# Output_buffer_C_and_D_Page_3.net
KiCad netlist of a schematic drawn in Altium Designer
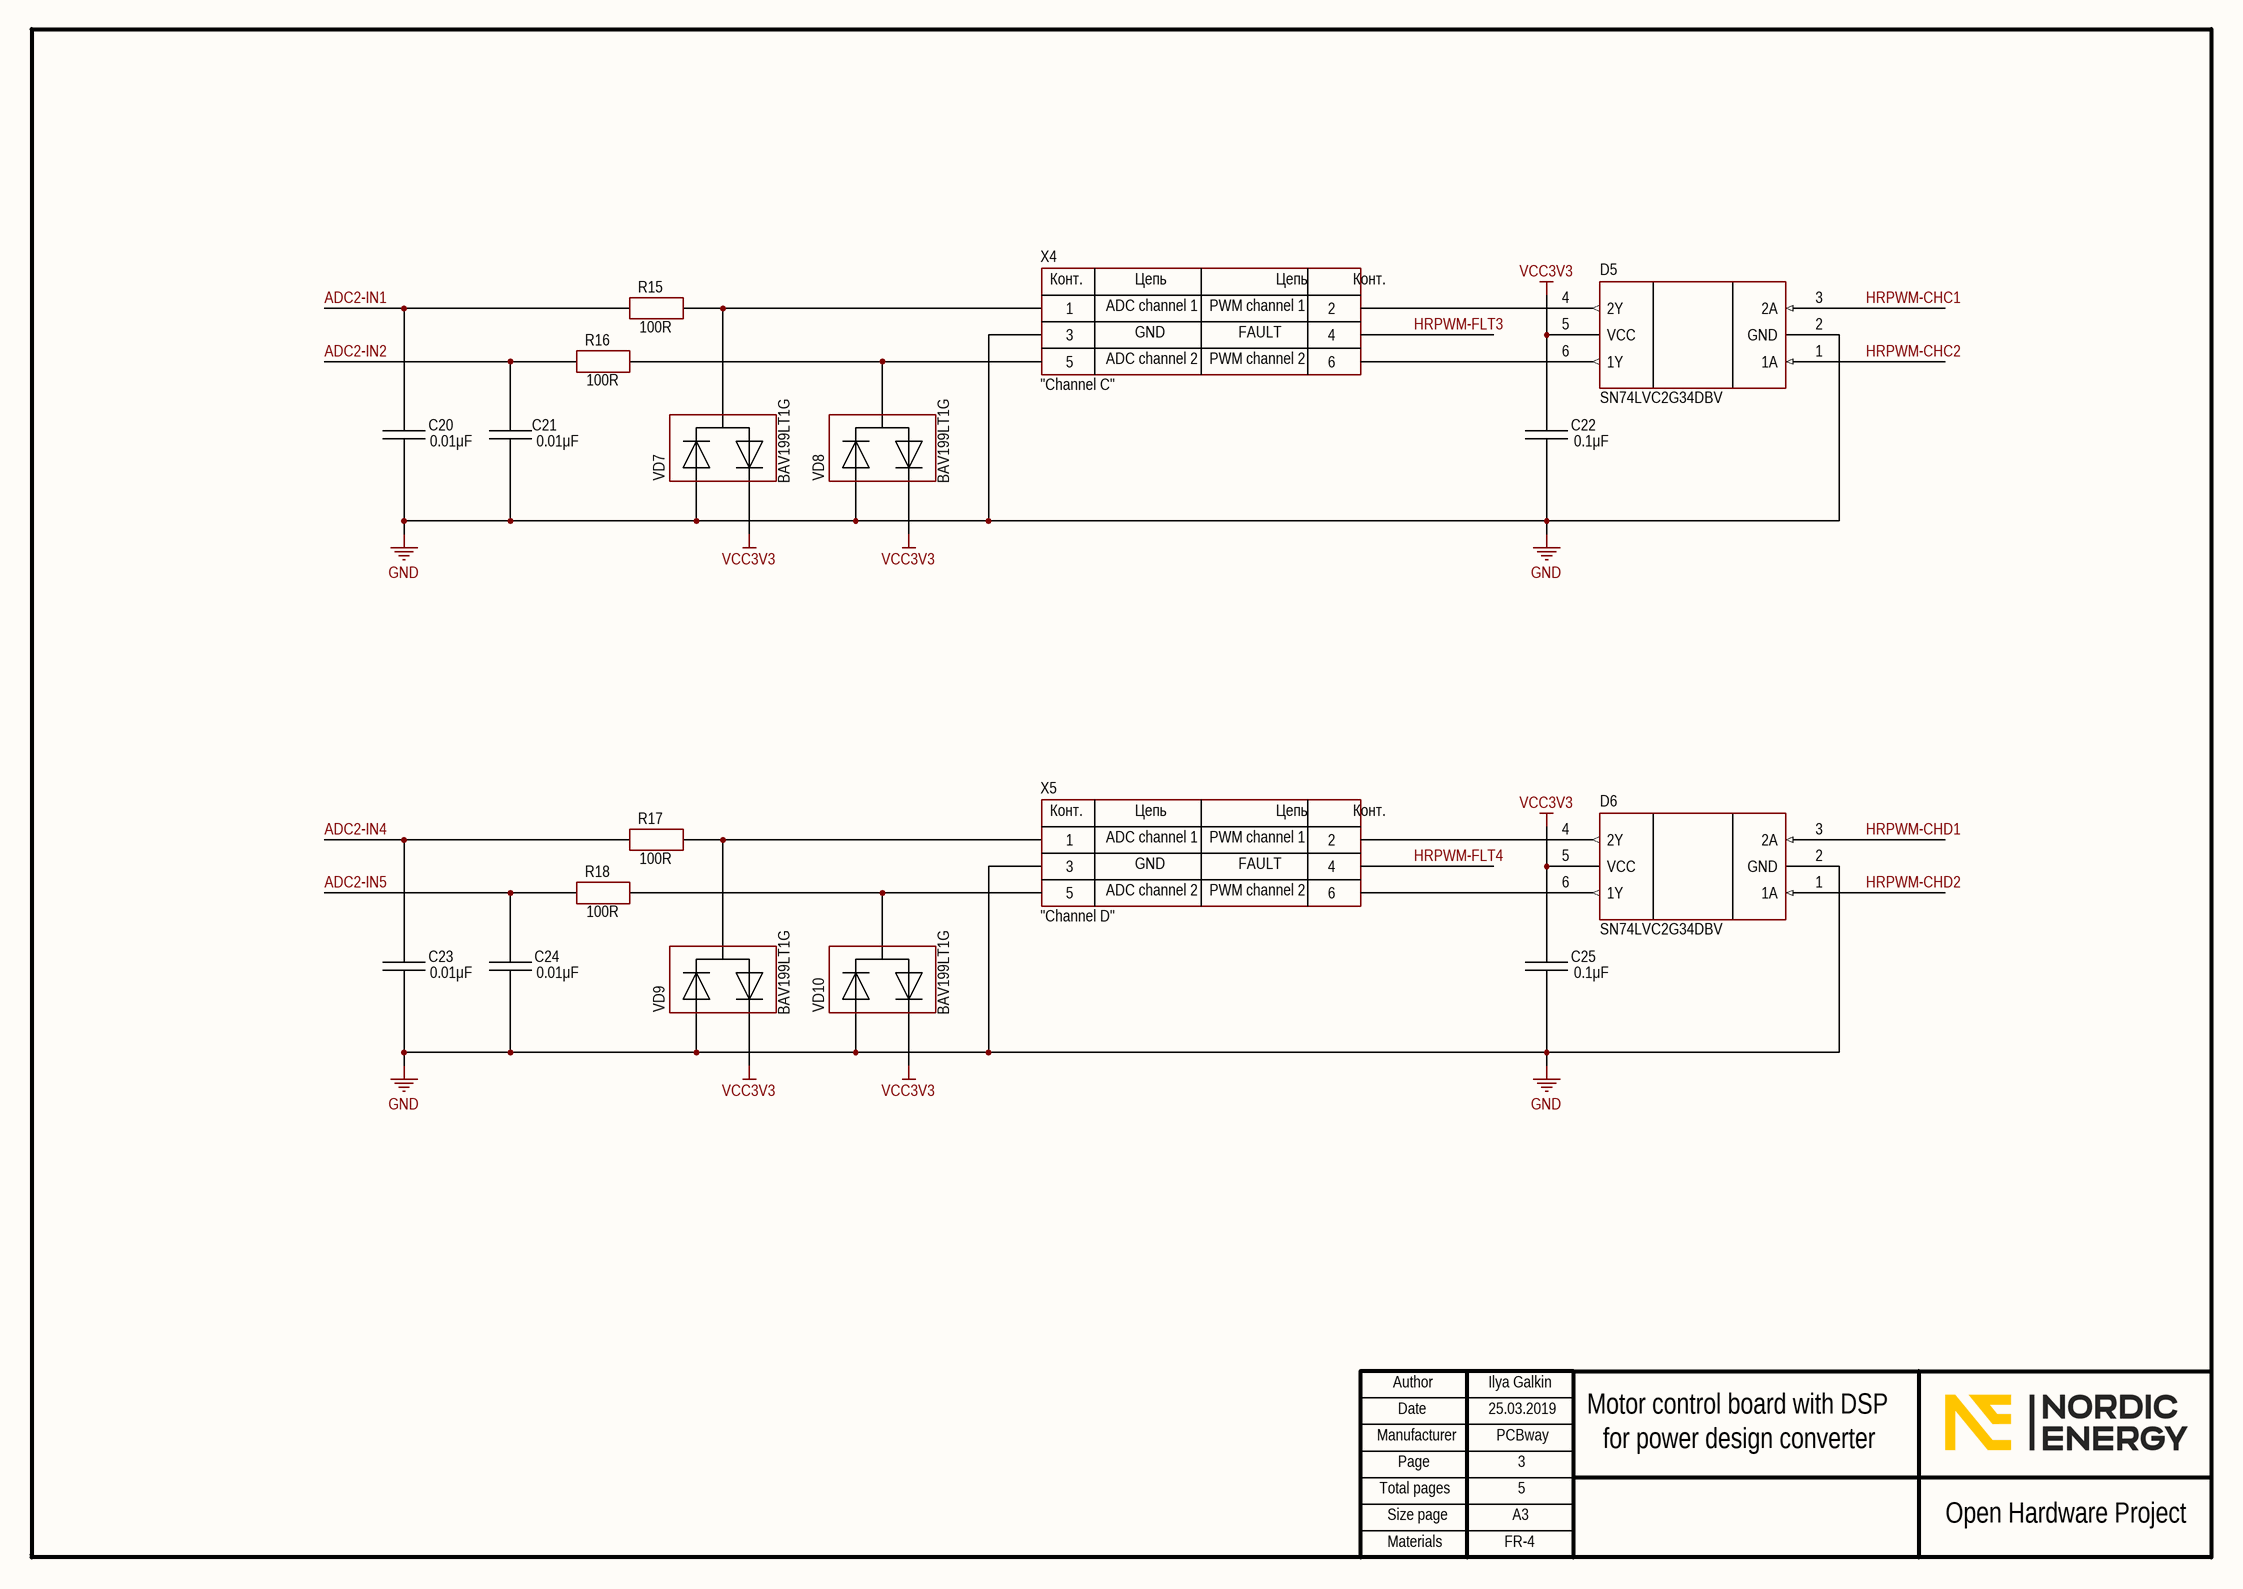
[diagram p0: Output buffer C and D. Page 3.SchDoc]

(export (version "E")
  (design (tool "Eeschema 10.0.6"))
  (components
    (comp (ref "C20")
      (value "0.01μF")
      (footprint "CH0805C")
      (fields (field (name "MANUFACTURER") "Yageo"))
      (libsource (lib "Discrete") (part "Capacitor"))
    )
    (comp (ref "C21")
      (value "0.01μF")
      (footprint "CH0805C")
      (fields (field (name "MANUFACTURER") "Yageo"))
      (libsource (lib "Discrete") (part "Capacitor"))
    )
    (comp (ref "C22")
      (value "0.1μF")
      (footprint "CH0805C")
      (fields (field (name "MANUFACTURER") "Yageo"))
      (libsource (lib "Discrete") (part "Capacitor"))
    )
    (comp (ref "C23")
      (value "0.01μF")
      (footprint "CH0805C")
      (fields (field (name "MANUFACTURER") "Yageo"))
      (libsource (lib "Discrete") (part "Capacitor"))
    )
    (comp (ref "C24")
      (value "0.01μF")
      (footprint "CH0805C")
      (fields (field (name "MANUFACTURER") "Yageo"))
      (libsource (lib "Discrete") (part "Capacitor"))
    )
    (comp (ref "C25")
      (value "0.1μF")
      (footprint "CH0805C")
      (fields (field (name "MANUFACTURER") "Yageo"))
      (libsource (lib "Discrete") (part "Capacitor"))
    )
    (comp (ref "D5")
      (value "SN74LVC2G34DBV")
      (footprint "SOT23-6")
      (description "Buffer")
      (fields (field (name "MANUFACTURER") "Texas Instruments"))
      (libsource (lib "Analog") (part "SN74LVC2G34DBV"))
    )
    (comp (ref "D6")
      (value "SN74LVC2G34DBV")
      (footprint "SOT23-6")
      (description "Buffer")
      (fields (field (name "MANUFACTURER") "Texas Instruments"))
      (libsource (lib "Analog") (part "SN74LVC2G34DBV"))
    )
    (comp (ref "R15")
      (value "100R")
      (footprint "CH0805R")
      (fields (field (name "MANUFACTURER") "Yageo"))
      (libsource (lib "Discrete") (part "Resistor"))
    )
    (comp (ref "R16")
      (value "100R")
      (footprint "CH0805R")
      (fields (field (name "MANUFACTURER") "Yageo"))
      (libsource (lib "Discrete") (part "Resistor"))
    )
    (comp (ref "R17")
      (value "100R")
      (footprint "CH0805R")
      (fields (field (name "MANUFACTURER") "Yageo"))
      (libsource (lib "Discrete") (part "Resistor"))
    )
    (comp (ref "R18")
      (value "100R")
      (footprint "CH0805R")
      (fields (field (name "MANUFACTURER") "Yageo"))
      (libsource (lib "Discrete") (part "Resistor"))
    )
    (comp (ref "VD7")
      (value "BAV199LT1G")
      (footprint "SOT23_132")
      (fields (field (name "MANUFACTURER") "ON Semiconductor"))
      (libsource (lib "Diods") (part "Diod Array"))
    )
    (comp (ref "VD8")
      (value "BAV199LT1G")
      (footprint "SOT23_132")
      (fields (field (name "MANUFACTURER") "ON Semiconductor"))
      (libsource (lib "Diods") (part "Diod Array"))
    )
    (comp (ref "VD9")
      (value "BAV199LT1G")
      (footprint "SOT23_132")
      (fields (field (name "MANUFACTURER") "ON Semiconductor"))
      (libsource (lib "Diods") (part "Diod Array"))
    )
    (comp (ref "VD10")
      (value "BAV199LT1G")
      (footprint "SOT23_132")
      (fields (field (name "MANUFACTURER") "ON Semiconductor"))
      (libsource (lib "Diods") (part "Diod Array"))
    )
    (comp (ref "X4")
      (value "\"Channel C\"")
      (footprint "CON: PLD-6")
      (libsource (lib "Connectors") (part "6(2)-Connector"))
    )
    (comp (ref "X5")
      (value "\"Channel D\"")
      (footprint "CON: PLD-6")
      (libsource (lib "Connectors") (part "6(2)-Connector"))
    )
  )
  (nets
    (net (code "1") (name "/ADC2-IN1") (class "Default")
      (node (ref "C20") (pin "2") (pinfunction "2_2") (pintype "power_in"))
      (node (ref "R15") (pin "1") (pinfunction "1_1") (pintype "passive"))
    )
    (net (code "2") (name "/ADC2-IN2") (class "Default")
      (node (ref "C21") (pin "2") (pinfunction "2_2") (pintype "power_in"))
      (node (ref "R16") (pin "1") (pinfunction "1_1") (pintype "passive"))
    )
    (net (code "3") (name "/ADC2-IN4") (class "Default")
      (node (ref "C23") (pin "2") (pinfunction "2_2") (pintype "power_in"))
      (node (ref "R17") (pin "1") (pinfunction "1_1") (pintype "passive"))
    )
    (net (code "4") (name "/ADC2-IN5") (class "Default")
      (node (ref "C24") (pin "2") (pinfunction "2_2") (pintype "power_in"))
      (node (ref "R18") (pin "1") (pinfunction "1_1") (pintype "passive"))
    )
    (net (code "5") (name "/HRPWM-CHC1") (class "Default")
      (node (ref "D5") (pin "3") (pinfunction "2A_3") (pintype "input"))
    )
    (net (code "6") (name "/HRPWM-CHC2") (class "Default")
      (node (ref "D5") (pin "1") (pinfunction "1A_1") (pintype "input"))
    )
    (net (code "7") (name "/HRPWM-CHD1") (class "Default")
      (node (ref "D6") (pin "3") (pinfunction "2A_3") (pintype "input"))
    )
    (net (code "8") (name "/HRPWM-CHD2") (class "Default")
      (node (ref "D6") (pin "1") (pinfunction "1A_1") (pintype "input"))
    )
    (net (code "9") (name "/HRPWM-FLT3") (class "Default")
      (node (ref "X4") (pin "4") (pinfunction "4_4") (pintype "passive"))
    )
    (net (code "10") (name "/HRPWM-FLT4") (class "Default")
      (node (ref "X5") (pin "4") (pinfunction "4_4") (pintype "passive"))
    )
    (net (code "11") (name "GND") (class "Default")
      (node (ref "C20") (pin "1") (pinfunction "1_1") (pintype "power_in"))
      (node (ref "C21") (pin "1") (pinfunction "1_1") (pintype "power_in"))
      (node (ref "C22") (pin "1") (pinfunction "1_1") (pintype "power_in"))
      (node (ref "C23") (pin "1") (pinfunction "1_1") (pintype "power_in"))
      (node (ref "C24") (pin "1") (pinfunction "1_1") (pintype "power_in"))
      (node (ref "C25") (pin "1") (pinfunction "1_1") (pintype "power_in"))
      (node (ref "D5") (pin "2") (pinfunction "GND_2") (pintype "passive"))
      (node (ref "D6") (pin "2") (pinfunction "GND_2") (pintype "passive"))
      (node (ref "VD10") (pin "1") (pinfunction "1_1") (pintype "passive"))
      (node (ref "VD7") (pin "1") (pinfunction "1_1") (pintype "passive"))
      (node (ref "VD8") (pin "1") (pinfunction "1_1") (pintype "passive"))
      (node (ref "VD9") (pin "1") (pinfunction "1_1") (pintype "passive"))
      (node (ref "X4") (pin "3") (pinfunction "3_3") (pintype "passive"))
      (node (ref "X5") (pin "3") (pinfunction "3_3") (pintype "passive"))
    )
    (net (code "12") (name "Net-(D5-1Y)") (class "Default")
      (node (ref "D5") (pin "6") (pinfunction "1Y_6") (pintype "output"))
      (node (ref "X4") (pin "6") (pinfunction "6_6") (pintype "power_in"))
    )
    (net (code "13") (name "Net-(D5-2Y)") (class "Default")
      (node (ref "D5") (pin "4") (pinfunction "2Y_4") (pintype "output"))
      (node (ref "X4") (pin "2") (pinfunction "2_2") (pintype "passive"))
    )
    (net (code "14") (name "Net-(D6-1Y)") (class "Default")
      (node (ref "D6") (pin "6") (pinfunction "1Y_6") (pintype "output"))
      (node (ref "X5") (pin "6") (pinfunction "6_6") (pintype "power_in"))
    )
    (net (code "15") (name "Net-(D6-2Y)") (class "Default")
      (node (ref "D6") (pin "4") (pinfunction "2Y_4") (pintype "output"))
      (node (ref "X5") (pin "2") (pinfunction "2_2") (pintype "passive"))
    )
    (net (code "16") (name "Net-(R15-Pad2)") (class "Default")
      (node (ref "R15") (pin "2") (pinfunction "2_2") (pintype "passive"))
      (node (ref "VD7") (pin "3") (pinfunction "3_3") (pintype "passive"))
      (node (ref "X4") (pin "1") (pinfunction "1_1") (pintype "passive"))
    )
    (net (code "17") (name "Net-(R16-Pad2)") (class "Default")
      (node (ref "R16") (pin "2") (pinfunction "2_2") (pintype "passive"))
      (node (ref "VD8") (pin "3") (pinfunction "3_3") (pintype "passive"))
      (node (ref "X4") (pin "5") (pinfunction "5_5") (pintype "power_in"))
    )
    (net (code "18") (name "Net-(R17-Pad2)") (class "Default")
      (node (ref "R17") (pin "2") (pinfunction "2_2") (pintype "passive"))
      (node (ref "VD9") (pin "3") (pinfunction "3_3") (pintype "passive"))
      (node (ref "X5") (pin "1") (pinfunction "1_1") (pintype "passive"))
    )
    (net (code "19") (name "Net-(R18-Pad2)") (class "Default")
      (node (ref "R18") (pin "2") (pinfunction "2_2") (pintype "passive"))
      (node (ref "VD10") (pin "3") (pinfunction "3_3") (pintype "passive"))
      (node (ref "X5") (pin "5") (pinfunction "5_5") (pintype "power_in"))
    )
    (net (code "20") (name "VCC3V3") (class "Default")
      (node (ref "C22") (pin "2") (pinfunction "2_2") (pintype "power_in"))
      (node (ref "C25") (pin "2") (pinfunction "2_2") (pintype "power_in"))
      (node (ref "D5") (pin "5") (pinfunction "VCC_5") (pintype "passive"))
      (node (ref "D6") (pin "5") (pinfunction "VCC_5") (pintype "passive"))
      (node (ref "VD10") (pin "2") (pinfunction "2_2") (pintype "passive"))
      (node (ref "VD7") (pin "2") (pinfunction "2_2") (pintype "passive"))
      (node (ref "VD8") (pin "2") (pinfunction "2_2") (pintype "passive"))
      (node (ref "VD9") (pin "2") (pinfunction "2_2") (pintype "passive"))
    )
  )
)
